# Instrutmentation_Design.net
KiCad netlist of a schematic drawn in Altium Designer
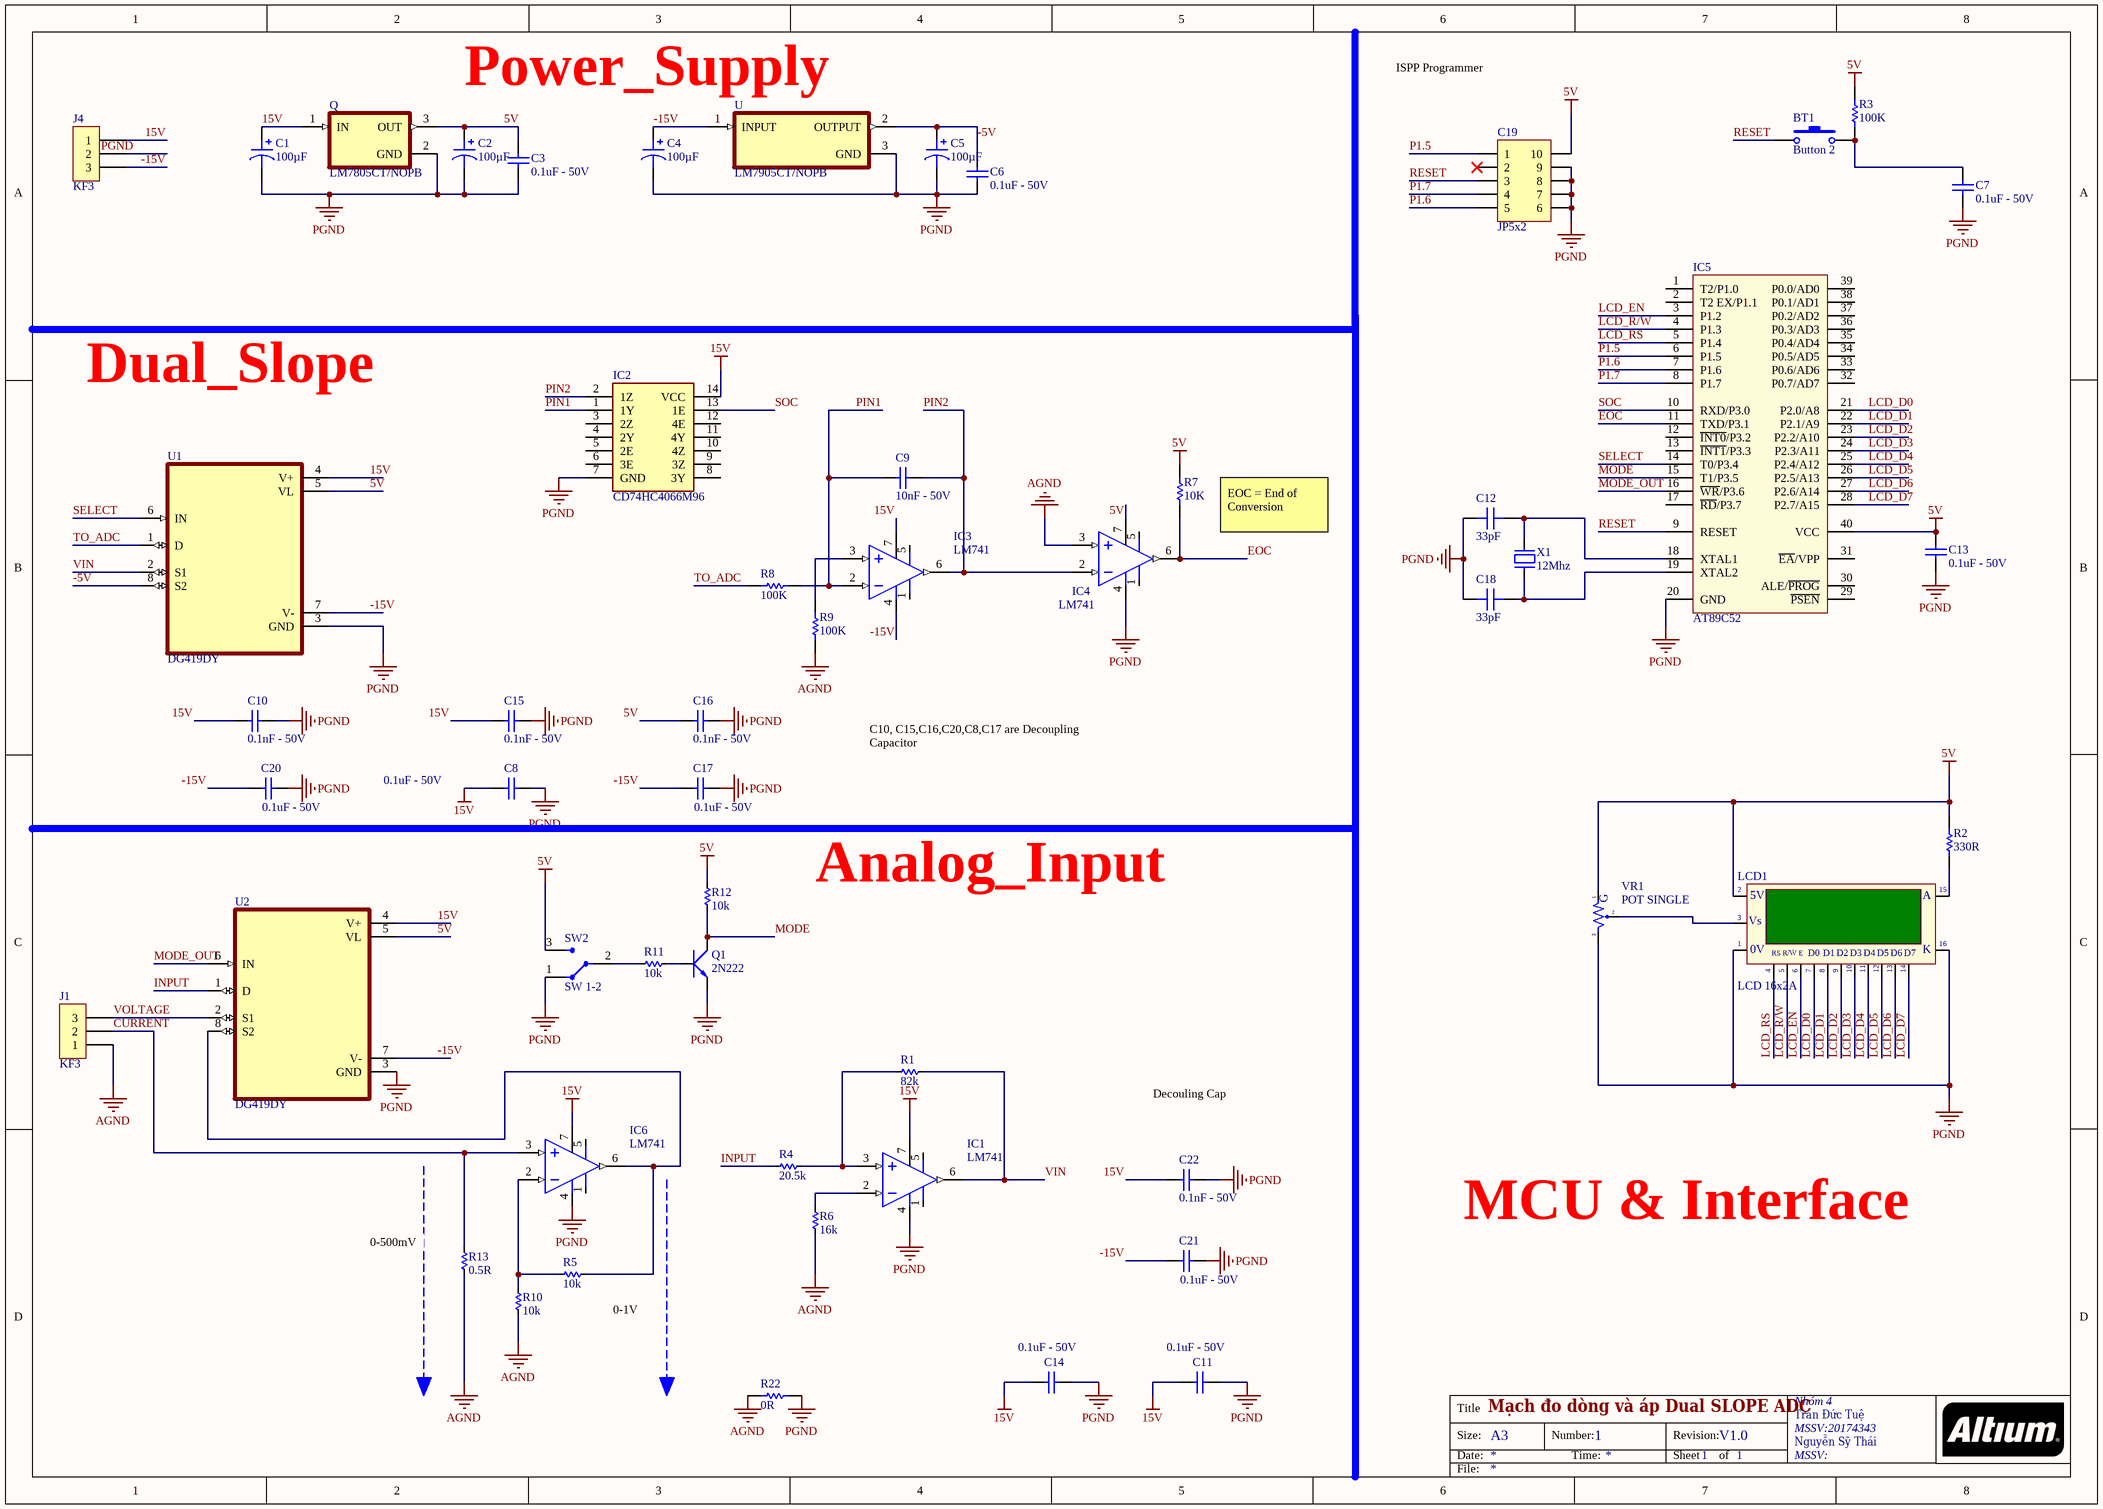
[diagram p0: Instrutmentation_Design.SchDoc]

(export (version "E")
  (design (tool "Eeschema 10.0.6"))
  (components
    (comp (ref "BT1")
      (value "Button 2")
      (footprint "4341x10438x6_6x3.5x4.3")
      (description "Button 2 Pin no Sheld")
      (libsource (lib "Library") (part "Button 2"))
    )
    (comp (ref "C1")
      (value "100µF")
      (footprint "CAP TH ALUM ELEC D8.00mm S3.50mm H12.50mm")
      (description "CAP ALUM 100UF 20% 50V RADIAL")
      (fields
        (field (name "PART NUMBER") "ECA-1HM101")
        (field (name "MANUFACTURER") "Panasonic Electronic Components")
      )
      (libsource (lib "Celestial Altium Library - altium_library") (part "Polarised Capacitor"))
    )
    (comp (ref "C2")
      (value "100µF")
      (footprint "CAP TH ALUM ELEC D8.00mm S3.50mm H12.50mm")
      (description "CAP ALUM 100UF 20% 50V RADIAL")
      (fields
        (field (name "PART NUMBER") "ECA-1HM101")
        (field (name "MANUFACTURER") "Panasonic Electronic Components")
      )
      (libsource (lib "Celestial Altium Library - altium_library") (part "Polarised Capacitor"))
    )
    (comp (ref "C3")
      (value "0.1uF - 50V")
      (footprint "CAPC_0603_N")
      (description "CAP CER 0.1UF 50V X7R 0603")
      (fields (field (name "PARTNUMBER") "C0603X7R104K500NT") (field (name "CREATOR") "ThangND"))
      (libsource (lib "MKP_lib") (part "CAP"))
    )
    (comp (ref "C4")
      (value "100µF")
      (footprint "CAP TH ALUM ELEC D8.00mm S3.50mm H12.50mm")
      (description "CAP ALUM 100UF 20% 50V RADIAL")
      (fields
        (field (name "PART NUMBER") "ECA-1HM101")
        (field (name "MANUFACTURER") "Panasonic Electronic Components")
      )
      (libsource (lib "Celestial Altium Library - altium_library") (part "Polarised Capacitor"))
    )
    (comp (ref "C5")
      (value "100µF")
      (footprint "CAP TH ALUM ELEC D8.00mm S3.50mm H12.50mm")
      (description "CAP ALUM 100UF 20% 50V RADIAL")
      (fields
        (field (name "PART NUMBER") "ECA-1HM101")
        (field (name "MANUFACTURER") "Panasonic Electronic Components")
      )
      (libsource (lib "Celestial Altium Library - altium_library") (part "Polarised Capacitor"))
    )
    (comp (ref "C6")
      (value "0.1uF - 50V")
      (footprint "CAPC_0603_N")
      (description "CAP CER 0.1UF 50V X7R 0603")
      (fields (field (name "PARTNUMBER") "C0603X7R104K500NT") (field (name "CREATOR") "ThangND"))
      (libsource (lib "MKP_lib") (part "CAP"))
    )
    (comp (ref "C7")
      (value "0.1uF - 50V")
      (footprint "CAPC_0603_N")
      (description "CAP CER 0.1UF 50V X7R 0603")
      (fields (field (name "PARTNUMBER") "C0603X7R104K500NT") (field (name "CREATOR") "ThangND"))
      (libsource (lib "MKP_lib") (part "CAP"))
    )
    (comp (ref "C8")
      (value "0.1uF - 50V")
      (footprint "CAPC_0603_N")
      (description "CAP CER 0.1UF 50V X7R 0603")
      (fields (field (name "PARTNUMBER") "C0603X7R104K500NT") (field (name "CREATOR") "ThangND"))
      (libsource (lib "MKP_lib") (part "CAP"))
    )
    (comp (ref "C9")
      (value "10nF - 50V")
      (footprint "CAPC_0603_N")
      (description "CAP CER 10000PF 50V X7R 0603")
      (fields (field (name "PARTNUMBER") "C0603X7R103J500NT") (field (name "CREATOR") "ThangND"))
      (libsource (lib "MKP_lib") (part "CAP"))
    )
    (comp (ref "C10")
      (value "0.1nF - 50V")
      (footprint "CAPC_0603_N")
      (description "CAP CER 100PF 50V X7R 0603")
      (fields (field (name "PARTNUMBER") "CL10B101KB8NNNC") (field (name "CREATOR") "ThangND"))
      (libsource (lib "MKP_lib") (part "CAP"))
    )
    (comp (ref "C11")
      (value "0.1uF - 50V")
      (footprint "CAPC_0603_N")
      (description "CAP CER 0.1UF 50V X7R 0603")
      (fields (field (name "PARTNUMBER") "C0603X7R104K500NT") (field (name "CREATOR") "ThangND"))
      (libsource (lib "MKP_lib") (part "CAP"))
    )
    (comp (ref "C12")
      (value "33pF")
      (footprint "CAP 0805_2012")
      (description "CAP CER 33PF 250V C0G/NP0 0805")
      (fields (field (name "PART NUMBER") "CBR08C330JAGAC") (field (name "MANUFACTURER") "KEMET"))
      (libsource (lib "Celestial Altium Library - altium_library") (part "Capacitor"))
    )
    (comp (ref "C13")
      (value "0.1uF - 50V")
      (footprint "CAPC_0603_N")
      (description "CAP CER 0.1UF 50V X7R 0603")
      (fields (field (name "PARTNUMBER") "C0603X7R104K500NT") (field (name "CREATOR") "ThangND"))
      (libsource (lib "MKP_lib") (part "CAP"))
    )
    (comp (ref "C14")
      (value "0.1uF - 50V")
      (footprint "CAPC_0603_N")
      (description "CAP CER 0.1UF 50V X7R 0603")
      (fields (field (name "PARTNUMBER") "C0603X7R104K500NT") (field (name "CREATOR") "ThangND"))
      (libsource (lib "MKP_lib") (part "CAP"))
    )
    (comp (ref "C15")
      (value "0.1nF - 50V")
      (footprint "CAPC_0603_N")
      (description "CAP CER 100PF 50V X7R 0603")
      (fields (field (name "PARTNUMBER") "CL10B101KB8NNNC") (field (name "CREATOR") "ThangND"))
      (libsource (lib "MKP_lib") (part "CAP"))
    )
    (comp (ref "C16")
      (value "0.1nF - 50V")
      (footprint "CAPC_0603_N")
      (description "CAP CER 100PF 50V X7R 0603")
      (fields (field (name "PARTNUMBER") "CL10B101KB8NNNC") (field (name "CREATOR") "ThangND"))
      (libsource (lib "MKP_lib") (part "CAP"))
    )
    (comp (ref "C17")
      (value "0.1uF - 50V")
      (footprint "CAPC_0603_N")
      (description "CAP CER 0.1UF 50V X7R 0603")
      (fields (field (name "PARTNUMBER") "CL10B104KB8NNNC") (field (name "CREATOR") "ThangND"))
      (libsource (lib "MKP_lib") (part "CAP"))
    )
    (comp (ref "C18")
      (value "33pF")
      (footprint "CAP 0805_2012")
      (description "CAP CER 33PF 250V C0G/NP0 0805")
      (fields (field (name "PART NUMBER") "CBR08C330JAGAC") (field (name "MANUFACTURER") "KEMET"))
      (libsource (lib "Celestial Altium Library - altium_library") (part "Capacitor"))
    )
    (comp (ref "C19")
      (value "JP5x2")
      (footprint "JP5-D2T")
      (description "WR-PHD 2.54 mm Dual Socket Header")
      (fields
        (field (name "MANUFACTURER") "Würth Elektronik eiSos GmbH")
        (field (name "PARTNO") "61301021821")
        (field (name "CREATED BY") "Karrer Zheng")
      )
      (libsource (lib "LIBRARY TuHu") (part "JP5x2"))
    )
    (comp (ref "C20")
      (value "0.1uF - 50V")
      (footprint "CAPC_0603_N")
      (description "CAP CER 0.1UF 50V X7R 0603")
      (fields (field (name "PARTNUMBER") "CL10B104KB8NNNC") (field (name "CREATOR") "ThangND"))
      (libsource (lib "MKP_lib") (part "CAP"))
    )
    (comp (ref "C21")
      (value "0.1uF - 50V")
      (footprint "CAPC_0603_N")
      (description "CAP CER 0.1UF 50V X7R 0603")
      (fields (field (name "PARTNUMBER") "CL10B104KB8NNNC") (field (name "CREATOR") "ThangND"))
      (libsource (lib "MKP_lib") (part "CAP"))
    )
    (comp (ref "C22")
      (value "0.1nF - 50V")
      (footprint "CAPC_0603_N")
      (description "CAP CER 100PF 50V X7R 0603")
      (fields (field (name "PARTNUMBER") "CL10B101KB8NNNC") (field (name "CREATOR") "ThangND"))
      (libsource (lib "MKP_lib") (part "CAP"))
    )
    (comp (ref "IC1")
      (value "LM741")
      (footprint "SO8")
      (description "Single OA")
      (libsource (lib "LIBRARY TuHu") (part "LM741"))
    )
    (comp (ref "IC2")
      (value "CD74HC4066M96")
      (footprint "SamacSys:SOIC127P600X175-14N")
      (description "Integrated Circuit")
      (fields (field (name "MOUSER PART NUMBER") "595-CD74HC4066M96"))
      (libsource (lib "*") (part "CD74HC4066M96"))
    )
    (comp (ref "IC3")
      (value "LM741")
      (footprint "SO8")
      (description "Single OA")
      (libsource (lib "LIBRARY TuHu") (part "LM741"))
    )
    (comp (ref "IC4")
      (value "LM741")
      (footprint "SO8")
      (description "Single OA")
      (libsource (lib "LIBRARY TuHu") (part "LM741"))
    )
    (comp (ref "IC5")
      (value "AT89C52")
      (footprint "DIP40/W0.6")
      (description "Atmel AT89C52, 8k Byte Flash Memory , 40 Pin")
      (libsource (lib "syhaunguyen") (part "AT89C52"))
    )
    (comp (ref "IC6")
      (value "LM741")
      (footprint "SO8")
      (description "Single OA")
      (libsource (lib "LIBRARY TuHu") (part "LM741"))
    )
    (comp (ref "J1")
      (value "KF3")
      (footprint "KF3-5.08")
      (fields
        (field (name "MANUFACTURER") "Würth Elektronik eiSos GmbH")
        (field (name "PARTNO") "691103110003")
        (field (name "CREATED BY") "Karrer Zheng")
      )
      (libsource (lib "LIBRARY TuHu") (part "KF3"))
    )
    (comp (ref "J4")
      (value "KF3")
      (footprint "KF3-5.08")
      (fields
        (field (name "MANUFACTURER") "Würth Elektronik eiSos GmbH")
        (field (name "PARTNO") "691103110003")
        (field (name "CREATED BY") "Karrer Zheng")
      )
      (libsource (lib "") (part "KF3_1"))
    )
    (comp (ref "LCD1")
      (value "LCD 16x2A")
      (footprint "JP16-C1T")
      (description "LCD dipslay 16 char, 2 line")
      (libsource (lib "LIBRARY TuHu") (part "LCD16x2A"))
    )
    (comp (ref "Q")
      (value "LM7805CT/NOPB")
      (footprint "SnapEDApcb:TO254P1054X470X2600-3")
      (description "Linear Voltage Regulator IC 1 Output 1A TO-220-3")
      (fields (field (name "MP") "LM7805CT") (field (name "MF") "ON Semiconductor"))
      (libsource (lib "SnapEDAsch") (part "LM7805CT/NOPB"))
    )
    (comp (ref "Q1")
      (value "2N222")
      (footprint "SOT23-231")
      (description "NPN 600mW, ECB")
      (libsource (lib "LIBRARY TuHu") (part "2N222"))
    )
    (comp (ref "R1")
      (value "82k")
      (footprint "RES-SMD-0805")
      (description "Resistor")
      (fields
        (field (name "MANUFACTURER") "Generic Components")
        (field (name "PUBLISHER") "Altium Hobart Technology Centre")
      )
      (libsource (lib "LIBRARY TuHu") (part "Res-SMD"))
    )
    (comp (ref "R2")
      (value "330R")
      (footprint "RESC_0603_N")
      (description "RES SMD 330 OHM 1% 1/10W 0603")
      (fields (field (name "PARTNUMBER") "RI0603L3300FT") (field (name "CREATOR") "anhdn"))
      (libsource (lib "MKP_lib") (part "RES"))
    )
    (comp (ref "R3")
      (value "100K")
      (footprint "RESC_0805_N")
      (description "RES SMD 100K OHM 5% 1/8W 0805")
      (fields (field (name "PARTNUMBER") "RC0805JR-07100KL") (field (name "CREATOR") "Tunn"))
      (libsource (lib "MKP_lib") (part "RES"))
    )
    (comp (ref "R4")
      (value "20.5k")
      (footprint "RES-SMD-0805")
      (description "Resistor")
      (fields
        (field (name "MANUFACTURER") "Generic Components")
        (field (name "PUBLISHER") "Altium Hobart Technology Centre")
      )
      (libsource (lib "LIBRARY TuHu") (part "Res-SMD"))
    )
    (comp (ref "R5")
      (value "10k")
      (footprint "RES-SMD-0805")
      (description "Resistor")
      (fields
        (field (name "MANUFACTURER") "Generic Components")
        (field (name "PUBLISHER") "Altium Hobart Technology Centre")
      )
      (libsource (lib "LIBRARY TuHu") (part "Res-SMD"))
    )
    (comp (ref "R6")
      (value "16k")
      (footprint "RES-SMD-0805")
      (description "Resistor")
      (fields
        (field (name "MANUFACTURER") "Generic Components")
        (field (name "PUBLISHER") "Altium Hobart Technology Centre")
      )
      (libsource (lib "LIBRARY TuHu") (part "Res-SMD"))
    )
    (comp (ref "R7")
      (value "10K")
      (footprint "RESC_0603_N")
      (description "RES SMD 10K OHM 1% 1/10W 0603")
      (fields (field (name "PARTNUMBER") "RI0603L1002FT") (field (name "CREATOR") "anhdn"))
      (libsource (lib "MKP_lib") (part "RES"))
    )
    (comp (ref "R8")
      (value "100K")
      (footprint "RESC_0805_N")
      (description "RES SMD 100K OHM 5% 1/8W 0805")
      (fields (field (name "PARTNUMBER") "RC0805JR-07100KL") (field (name "CREATOR") "Tunn"))
      (libsource (lib "MKP_lib") (part "RES"))
    )
    (comp (ref "R9")
      (value "100K")
      (footprint "RESC_0805_N")
      (description "RES SMD 100K OHM 5% 1/8W 0805")
      (fields (field (name "PARTNUMBER") "RC0805JR-07100KL") (field (name "CREATOR") "Tunn"))
      (libsource (lib "MKP_lib") (part "RES"))
    )
    (comp (ref "R10")
      (value "10k")
      (footprint "RES-SMD-0805")
      (description "Resistor")
      (fields
        (field (name "MANUFACTURER") "Generic Components")
        (field (name "PUBLISHER") "Altium Hobart Technology Centre")
      )
      (libsource (lib "LIBRARY TuHu") (part "Res-SMD"))
    )
    (comp (ref "R11")
      (value "10k")
      (footprint "RES-SMD-0805")
      (description "Resistor")
      (fields
        (field (name "MANUFACTURER") "Generic Components")
        (field (name "PUBLISHER") "Altium Hobart Technology Centre")
      )
      (libsource (lib "LIBRARY TuHu") (part "Res-SMD"))
    )
    (comp (ref "R12")
      (value "10k")
      (footprint "RES-SMD-0805")
      (description "Resistor")
      (fields
        (field (name "MANUFACTURER") "Generic Components")
        (field (name "PUBLISHER") "Altium Hobart Technology Centre")
      )
      (libsource (lib "LIBRARY TuHu") (part "Res-SMD"))
    )
    (comp (ref "R13")
      (value "0.5R")
      (footprint "RES-SMD-1206")
      (description "Resistor")
      (fields
        (field (name "MANUFACTURER") "Generic Components")
        (field (name "PUBLISHER") "Altium Hobart Technology Centre")
      )
      (libsource (lib "LIBRARY TuHu") (part "Res-SMD"))
    )
    (comp (ref "R22")
      (value "0R")
      (footprint "RESC_0805_N")
      (description "RES SMD 0 OHM JUMPER 1/8W 0805")
      (fields (field (name "PARTNUMBER") "RC0805JR-070RL") (field (name "CREATOR") "anhdn"))
      (libsource (lib "MKP_lib") (part "RES"))
    )
    (comp (ref "SW2")
      (value "SW 1-2")
      (footprint "450301014042")
      (description "Switch 1-2 Pin")
      (libsource (lib "Library") (part "SW 1-2"))
    )
    (comp (ref "U")
      (value "LM7905CT/NOPB")
      (footprint "TO254P1054X470X1955-3:TO254P1054X470X1955-3")
      (description "1.5-A, negative linear voltage regulator 3-TO-220 0 to 125")
      (fields (field (name "MF") "Texas Instruments"))
      (libsource (lib "LM7905CT_NOPB") (part "LM7905CT/NOPB"))
    )
    (comp (ref "U1")
      (value "DG419DY")
      (footprint "SOIC127P600X175-8N:SOIC127P600X175-8N")
      (libsource (lib "DG419DY") (part "DG419DY"))
    )
    (comp (ref "U2")
      (value "DG419DY")
      (footprint "SOIC127P600X175-8N:SOIC127P600X175-8N")
      (libsource (lib "DG419DY") (part "DG419DY"))
    )
    (comp (ref "VR1")
      (value "POT SINGLE")
      (footprint "POTSD 3296V")
      (description "Var Resistor")
      (libsource (lib "Library") (part "POT SINGLE"))
    )
    (comp (ref "X1")
      (value "12Mhz")
      (footprint "XT2")
      (description "Crystal, 32.768 KHz, -40 to 85 degC, 3.2 x 1.5 x 0.9 mm SMD")
      (libsource (lib "LIBRARY TuHu") (part "XT2"))
    )
  )
  (nets
    (net (code "1") (name "/-5V") (class "Default")
      (node (ref "C5") (pin "1") (pinfunction "1_1") (pintype "passive"))
      (node (ref "C6") (pin "2") (pinfunction "2_2") (pintype "passive"))
      (node (ref "U") (pin "2") (pinfunction "OUTPUT_2") (pintype "output"))
      (node (ref "U1") (pin "8") (pinfunction "S2_8") (pintype "bidirectional"))
    )
    (net (code "2") (name "/-15V") (class "Default")
      (node (ref "C17") (pin "1") (pinfunction "1_1") (pintype "passive"))
      (node (ref "C20") (pin "1") (pinfunction "1_1") (pintype "passive"))
      (node (ref "C21") (pin "1") (pinfunction "1_1") (pintype "passive"))
      (node (ref "C4") (pin "1") (pinfunction "1_1") (pintype "passive"))
      (node (ref "IC3") (pin "4") (pinfunction "-V_4") (pintype "passive"))
      (node (ref "J4") (pin "3") (pinfunction "3_3") (pintype "passive"))
      (node (ref "U") (pin "1") (pinfunction "INPUT_1") (pintype "input"))
      (node (ref "U1") (pin "7") (pinfunction "V-_7") (pintype "power_in"))
      (node (ref "U2") (pin "7") (pinfunction "V-_7") (pintype "power_in"))
    )
    (net (code "3") (name "/CURRENT") (class "Default")
      (node (ref "IC6") (pin "3") (pinfunction "IN+_3") (pintype "input"))
      (node (ref "J1") (pin "2") (pinfunction "2_2") (pintype "passive"))
      (node (ref "R13") (pin "2") (pinfunction "2_2") (pintype "passive"))
    )
    (net (code "4") (name "/EOC") (class "Default")
      (node (ref "IC4") (pin "6") (pinfunction "OUT_6") (pintype "output"))
      (node (ref "IC5") (pin "11") (pinfunction "TXD/P3.1_11") (pintype "passive"))
      (node (ref "R7") (pin "2") (pinfunction "2_2") (pintype "passive"))
    )
    (net (code "5") (name "/INPUT") (class "Default")
      (node (ref "R4") (pin "1") (pinfunction "1_1") (pintype "passive"))
      (node (ref "U2") (pin "1") (pinfunction "D_1") (pintype "bidirectional"))
    )
    (net (code "6") (name "/LCD_D0") (class "Default")
      (node (ref "IC5") (pin "21") (pinfunction "P2.0/A8_21") (pintype "passive"))
      (node (ref "LCD1") (pin "7") (pinfunction "D0_7") (pintype "passive"))
    )
    (net (code "7") (name "/LCD_D1") (class "Default")
      (node (ref "IC5") (pin "22") (pinfunction "P2.1/A9_22") (pintype "passive"))
      (node (ref "LCD1") (pin "8") (pinfunction "D1_8") (pintype "passive"))
    )
    (net (code "8") (name "/LCD_D2") (class "Default")
      (node (ref "IC5") (pin "23") (pinfunction "P2.2/A10_23") (pintype "passive"))
      (node (ref "LCD1") (pin "9") (pinfunction "D2_9") (pintype "passive"))
    )
    (net (code "9") (name "/LCD_D3") (class "Default")
      (node (ref "IC5") (pin "24") (pinfunction "P2.3/A11_24") (pintype "passive"))
      (node (ref "LCD1") (pin "10") (pinfunction "D3_10") (pintype "passive"))
    )
    (net (code "10") (name "/LCD_D4") (class "Default")
      (node (ref "IC5") (pin "25") (pinfunction "P2.4/A12_25") (pintype "passive"))
      (node (ref "LCD1") (pin "11") (pinfunction "D4_11") (pintype "passive"))
    )
    (net (code "11") (name "/LCD_D5") (class "Default")
      (node (ref "IC5") (pin "26") (pinfunction "P2.5/A13_26") (pintype "passive"))
      (node (ref "LCD1") (pin "12") (pinfunction "D5_12") (pintype "passive"))
    )
    (net (code "12") (name "/LCD_D6") (class "Default")
      (node (ref "IC5") (pin "27") (pinfunction "P2.6/A14_27") (pintype "passive"))
      (node (ref "LCD1") (pin "13") (pinfunction "D6_13") (pintype "passive"))
    )
    (net (code "13") (name "/LCD_D7") (class "Default")
      (node (ref "IC5") (pin "28") (pinfunction "P2.7/A15_28") (pintype "passive"))
      (node (ref "LCD1") (pin "14") (pinfunction "D7_14") (pintype "passive"))
    )
    (net (code "14") (name "/LCD_EN") (class "Default")
      (node (ref "IC5") (pin "3") (pinfunction "P1.2_3") (pintype "passive"))
      (node (ref "LCD1") (pin "6") (pinfunction "~{EN}_6") (pintype "passive"))
    )
    (net (code "15") (name "/LCD_RS") (class "Default")
      (node (ref "IC5") (pin "5") (pinfunction "P1.4_5") (pintype "passive"))
      (node (ref "LCD1") (pin "4") (pinfunction "RS_4") (pintype "passive"))
    )
    (net (code "16") (name "/LCD_R{slash}~{W}") (class "Default")
      (node (ref "IC5") (pin "4") (pinfunction "P1.3_4") (pintype "passive"))
      (node (ref "LCD1") (pin "5") (pinfunction "R/~{W}_5") (pintype "passive"))
    )
    (net (code "17") (name "/MODE") (class "Default")
      (node (ref "IC5") (pin "15") (pinfunction "T1/P3.5_15") (pintype "passive"))
      (node (ref "Q1") (pin "3") (pinfunction "C_3") (pintype "passive"))
      (node (ref "R12") (pin "1") (pinfunction "1_1") (pintype "passive"))
    )
    (net (code "18") (name "/MODE_OUT") (class "Default")
      (node (ref "IC5") (pin "16") (pinfunction "~{WR}/P3.6_16") (pintype "passive"))
      (node (ref "U2") (pin "6") (pinfunction "IN_6") (pintype "input"))
    )
    (net (code "19") (name "/P1.5") (class "Default")
      (node (ref "C19") (pin "1") (pinfunction "1_1") (pintype "passive"))
      (node (ref "IC5") (pin "6") (pinfunction "P1.5_6") (pintype "passive"))
    )
    (net (code "20") (name "/P1.6") (class "Default")
      (node (ref "C19") (pin "5") (pinfunction "5_5") (pintype "passive"))
      (node (ref "IC5") (pin "7") (pinfunction "P1.6_7") (pintype "passive"))
    )
    (net (code "21") (name "/P1.7") (class "Default")
      (node (ref "C19") (pin "4") (pinfunction "4_4") (pintype "passive"))
      (node (ref "IC5") (pin "8") (pinfunction "P1.7_8") (pintype "passive"))
    )
    (net (code "22") (name "/PIN1") (class "Default")
      (node (ref "C9") (pin "1") (pinfunction "1_1") (pintype "passive"))
      (node (ref "IC2") (pin "1") (pinfunction "1Y_1") (pintype "passive"))
      (node (ref "IC3") (pin "2") (pinfunction "IN-_2") (pintype "input"))
      (node (ref "R8") (pin "1") (pinfunction "1_1") (pintype "passive"))
    )
    (net (code "23") (name "/PIN2") (class "Default")
      (node (ref "C9") (pin "2") (pinfunction "2_2") (pintype "passive"))
      (node (ref "IC2") (pin "2") (pinfunction "1Z_2") (pintype "passive"))
      (node (ref "IC3") (pin "6") (pinfunction "OUT_6") (pintype "output"))
      (node (ref "IC4") (pin "2") (pinfunction "IN-_2") (pintype "input"))
    )
    (net (code "24") (name "/RESET") (class "Default")
      (node (ref "BT1") (pin "1") (pinfunction "1_1") (pintype "passive"))
      (node (ref "C19") (pin "3") (pinfunction "3_3") (pintype "passive"))
      (node (ref "IC5") (pin "9") (pinfunction "RESET_9") (pintype "passive"))
    )
    (net (code "25") (name "/SELECT") (class "Default")
      (node (ref "IC5") (pin "14") (pinfunction "T0/P3.4_14") (pintype "passive"))
      (node (ref "U1") (pin "6") (pinfunction "IN_6") (pintype "input"))
    )
    (net (code "26") (name "/SOC") (class "Default")
      (node (ref "IC2") (pin "13") (pinfunction "1E_13") (pintype "passive"))
      (node (ref "IC5") (pin "10") (pinfunction "RXD/P3.0_10") (pintype "passive"))
    )
    (net (code "27") (name "/TO_ADC") (class "Default")
      (node (ref "R8") (pin "2") (pinfunction "2_2") (pintype "passive"))
      (node (ref "U1") (pin "1") (pinfunction "D_1") (pintype "bidirectional"))
    )
    (net (code "28") (name "/VIN") (class "Default")
      (node (ref "IC1") (pin "6") (pinfunction "OUT_6") (pintype "output"))
      (node (ref "R1") (pin "2") (pinfunction "2_2") (pintype "passive"))
      (node (ref "U1") (pin "2") (pinfunction "S1_2") (pintype "bidirectional"))
    )
    (net (code "29") (name "/VOLTAGE") (class "Default")
      (node (ref "J1") (pin "3") (pinfunction "3_3") (pintype "passive"))
      (node (ref "U2") (pin "2") (pinfunction "S1_2") (pintype "bidirectional"))
    )
    (net (code "30") (name "5V") (class "Default")
      (node (ref "C13") (pin "1") (pinfunction "1_1") (pintype "passive"))
      (node (ref "C16") (pin "1") (pinfunction "1_1") (pintype "passive"))
      (node (ref "C19") (pin "10") (pinfunction "10_10") (pintype "passive"))
      (node (ref "C2") (pin "1") (pinfunction "1_1") (pintype "passive"))
      (node (ref "C3") (pin "2") (pinfunction "2_2") (pintype "passive"))
      (node (ref "IC4") (pin "7") (pinfunction "+V_7") (pintype "passive"))
      (node (ref "IC5") (pin "40") (pinfunction "VCC_40") (pintype "power_in"))
      (node (ref "LCD1") (pin "2") (pinfunction "VDD_2") (pintype "passive"))
      (node (ref "Q") (pin "3") (pinfunction "OUT_3") (pintype "output"))
      (node (ref "R12") (pin "2") (pinfunction "2_2") (pintype "passive"))
      (node (ref "R2") (pin "1") (pinfunction "1_1") (pintype "passive"))
      (node (ref "R3") (pin "1") (pinfunction "1_1") (pintype "passive"))
      (node (ref "R7") (pin "1") (pinfunction "1_1") (pintype "passive"))
      (node (ref "SW2") (pin "3") (pinfunction "I/O2_3") (pintype "passive"))
      (node (ref "U1") (pin "5") (pinfunction "VL_5") (pintype "power_in"))
      (node (ref "U2") (pin "5") (pinfunction "VL_5") (pintype "power_in"))
      (node (ref "VR1") (pin "1") (pinfunction "1_1") (pintype "passive"))
    )
    (net (code "31") (name "15V") (class "Default")
      (node (ref "C1") (pin "1") (pinfunction "1_1") (pintype "passive"))
      (node (ref "C10") (pin "1") (pinfunction "1_1") (pintype "passive"))
      (node (ref "C11") (pin "1") (pinfunction "1_1") (pintype "passive"))
      (node (ref "C14") (pin "1") (pinfunction "1_1") (pintype "passive"))
      (node (ref "C15") (pin "1") (pinfunction "1_1") (pintype "passive"))
      (node (ref "C22") (pin "1") (pinfunction "1_1") (pintype "passive"))
      (node (ref "C8") (pin "1") (pinfunction "1_1") (pintype "passive"))
      (node (ref "IC1") (pin "7") (pinfunction "+V_7") (pintype "passive"))
      (node (ref "IC2") (pin "14") (pinfunction "VCC_14") (pintype "passive"))
      (node (ref "IC3") (pin "7") (pinfunction "+V_7") (pintype "passive"))
      (node (ref "IC6") (pin "7") (pinfunction "+V_7") (pintype "passive"))
      (node (ref "J4") (pin "1") (pinfunction "1_1") (pintype "passive"))
      (node (ref "Q") (pin "1") (pinfunction "IN_1") (pintype "input"))
      (node (ref "U1") (pin "4") (pinfunction "V+_4") (pintype "power_in"))
      (node (ref "U2") (pin "4") (pinfunction "V+_4") (pintype "power_in"))
    )
    (net (code "32") (name "AGND") (class "Default")
      (node (ref "IC4") (pin "3") (pinfunction "IN+_3") (pintype "input"))
      (node (ref "J1") (pin "1") (pinfunction "1_1") (pintype "passive"))
      (node (ref "R10") (pin "2") (pinfunction "2_2") (pintype "passive"))
      (node (ref "R13") (pin "1") (pinfunction "1_1") (pintype "passive"))
      (node (ref "R22") (pin "2") (pinfunction "2_2") (pintype "passive"))
      (node (ref "R6") (pin "2") (pinfunction "2_2") (pintype "passive"))
      (node (ref "R9") (pin "2") (pinfunction "2_2") (pintype "passive"))
    )
    (net (code "33") (name "Net-(BT1-Pad2)") (class "Default")
      (node (ref "BT1") (pin "2") (pinfunction "2_2") (pintype "passive"))
      (node (ref "C7") (pin "2") (pinfunction "2_2") (pintype "passive"))
      (node (ref "R3") (pin "2") (pinfunction "2_2") (pintype "passive"))
    )
    (net (code "34") (name "Net-(IC1-IN+)") (class "Default")
      (node (ref "IC1") (pin "3") (pinfunction "IN+_3") (pintype "input"))
      (node (ref "R1") (pin "1") (pinfunction "1_1") (pintype "passive"))
      (node (ref "R4") (pin "2") (pinfunction "2_2") (pintype "passive"))
    )
    (net (code "35") (name "Net-(IC1-IN-)") (class "Default")
      (node (ref "IC1") (pin "2") (pinfunction "IN-_2") (pintype "input"))
      (node (ref "R6") (pin "1") (pinfunction "1_1") (pintype "passive"))
    )
    (net (code "36") (name "Net-(IC3-IN+)") (class "Default")
      (node (ref "IC3") (pin "3") (pinfunction "IN+_3") (pintype "input"))
      (node (ref "R9") (pin "1") (pinfunction "1_1") (pintype "passive"))
    )
    (net (code "37") (name "Net-(IC5-XTAL1)") (class "Default")
      (node (ref "C12") (pin "2") (pinfunction "2_2") (pintype "passive"))
      (node (ref "IC5") (pin "18") (pinfunction "XTAL1_18") (pintype "passive"))
      (node (ref "X1") (pin "2") (pinfunction "2_2") (pintype "passive"))
    )
    (net (code "38") (name "Net-(IC5-XTAL2)") (class "Default")
      (node (ref "C18") (pin "2") (pinfunction "2_2") (pintype "passive"))
      (node (ref "IC5") (pin "19") (pinfunction "XTAL2_19") (pintype "passive"))
      (node (ref "X1") (pin "1") (pinfunction "1_1") (pintype "passive"))
    )
    (net (code "39") (name "Net-(IC6-IN-)") (class "Default")
      (node (ref "IC6") (pin "2") (pinfunction "IN-_2") (pintype "input"))
      (node (ref "R10") (pin "1") (pinfunction "1_1") (pintype "passive"))
      (node (ref "R5") (pin "1") (pinfunction "1_1") (pintype "passive"))
    )
    (net (code "40") (name "Net-(IC6-OUT)") (class "Default")
      (node (ref "IC6") (pin "6") (pinfunction "OUT_6") (pintype "output"))
      (node (ref "R5") (pin "2") (pinfunction "2_2") (pintype "passive"))
      (node (ref "U2") (pin "8") (pinfunction "S2_8") (pintype "bidirectional"))
    )
    (net (code "41") (name "Net-(LCD1-A)") (class "Default")
      (node (ref "LCD1") (pin "15") (pinfunction "A_15") (pintype "passive"))
      (node (ref "R2") (pin "2") (pinfunction "2_2") (pintype "passive"))
    )
    (net (code "42") (name "Net-(LCD1-VEE)") (class "Default")
      (node (ref "LCD1") (pin "3") (pinfunction "VEE_3") (pintype "passive"))
      (node (ref "VR1") (pin "2") (pinfunction "2_2") (pintype "passive"))
    )
    (net (code "43") (name "Net-(Q1-B)") (class "Default")
      (node (ref "Q1") (pin "2") (pinfunction "B_2") (pintype "passive"))
      (node (ref "R11") (pin "2") (pinfunction "2_2") (pintype "passive"))
    )
    (net (code "44") (name "Net-(R11-Pad1)") (class "Default")
      (node (ref "R11") (pin "1") (pinfunction "1_1") (pintype "passive"))
      (node (ref "SW2") (pin "2") (pintype "passive"))
    )
    (net (code "45") (name "PGND") (class "Default")
      (node (ref "C1") (pin "2") (pinfunction "2_2") (pintype "passive"))
      (node (ref "C10") (pin "2") (pinfunction "2_2") (pintype "passive"))
      (node (ref "C11") (pin "2") (pinfunction "2_2") (pintype "passive"))
      (node (ref "C12") (pin "1") (pinfunction "1_1") (pintype "passive"))
      (node (ref "C13") (pin "2") (pinfunction "2_2") (pintype "passive"))
      (node (ref "C14") (pin "2") (pinfunction "2_2") (pintype "passive"))
      (node (ref "C15") (pin "2") (pinfunction "2_2") (pintype "passive"))
      (node (ref "C16") (pin "2") (pinfunction "2_2") (pintype "passive"))
      (node (ref "C17") (pin "2") (pinfunction "2_2") (pintype "passive"))
      (node (ref "C18") (pin "1") (pinfunction "1_1") (pintype "passive"))
      (node (ref "C19") (pin "6") (pinfunction "6_6") (pintype "passive"))
      (node (ref "C19") (pin "7") (pinfunction "7_7") (pintype "passive"))
      (node (ref "C19") (pin "8") (pinfunction "8_8") (pintype "passive"))
      (node (ref "C19") (pin "9") (pinfunction "9_9") (pintype "passive"))
      (node (ref "C2") (pin "2") (pinfunction "2_2") (pintype "passive"))
      (node (ref "C20") (pin "2") (pinfunction "2_2") (pintype "passive"))
      (node (ref "C21") (pin "2") (pinfunction "2_2") (pintype "passive"))
      (node (ref "C22") (pin "2") (pinfunction "2_2") (pintype "passive"))
      (node (ref "C3") (pin "1") (pinfunction "1_1") (pintype "passive"))
      (node (ref "C4") (pin "2") (pinfunction "2_2") (pintype "passive"))
      (node (ref "C5") (pin "2") (pinfunction "2_2") (pintype "passive"))
      (node (ref "C6") (pin "1") (pinfunction "1_1") (pintype "passive"))
      (node (ref "C7") (pin "1") (pinfunction "1_1") (pintype "passive"))
      (node (ref "C8") (pin "2") (pinfunction "2_2") (pintype "passive"))
      (node (ref "IC1") (pin "4") (pinfunction "-V_4") (pintype "passive"))
      (node (ref "IC2") (pin "7") (pinfunction "GND_7") (pintype "passive"))
      (node (ref "IC4") (pin "4") (pinfunction "-V_4") (pintype "passive"))
      (node (ref "IC5") (pin "20") (pinfunction "GND_20") (pintype "open_emitter"))
      (node (ref "IC6") (pin "4") (pinfunction "-V_4") (pintype "passive"))
      (node (ref "J4") (pin "2") (pinfunction "2_2") (pintype "passive"))
      (node (ref "LCD1") (pin "1") (pinfunction "GND_1") (pintype "passive"))
      (node (ref "LCD1") (pin "16") (pinfunction "K_16") (pintype "passive"))
      (node (ref "Q") (pin "2") (pinfunction "GND_2") (pintype "power_in"))
      (node (ref "Q1") (pin "1") (pinfunction "E_1") (pintype "passive"))
      (node (ref "R22") (pin "1") (pinfunction "1_1") (pintype "passive"))
      (node (ref "SW2") (pin "1") (pintype "passive"))
      (node (ref "U") (pin "3") (pinfunction "GND_3") (pintype "power_in"))
      (node (ref "U1") (pin "3") (pinfunction "GND_3") (pintype "power_in"))
      (node (ref "U2") (pin "3") (pinfunction "GND_3") (pintype "power_in"))
      (node (ref "VR1") (pin "3") (pinfunction "3_3") (pintype "passive"))
    )
    (net (code "46") (name "unconnected-(C19-Pad2)") (class "Default")
      (node (ref "C19") (pin "2") (pinfunction "2_2") (pintype "passive+no_connect"))
    )
    (net (code "47") (name "unconnected-(IC1-Vos-Pad1)") (class "Default")
      (node (ref "IC1") (pin "1") (pinfunction "Vos_1") (pintype "passive"))
    )
    (net (code "48") (name "unconnected-(IC1-Vos-Pad5)") (class "Default")
      (node (ref "IC1") (pin "5") (pinfunction "Vos_5") (pintype "passive"))
    )
    (net (code "49") (name "unconnected-(IC2-2E-Pad5)") (class "Default")
      (node (ref "IC2") (pin "5") (pinfunction "2E_5") (pintype "passive"))
    )
    (net (code "50") (name "unconnected-(IC2-2Y-Pad4)") (class "Default")
      (node (ref "IC2") (pin "4") (pinfunction "2Y_4") (pintype "passive"))
    )
    (net (code "51") (name "unconnected-(IC2-2Z-Pad3)") (class "Default")
      (node (ref "IC2") (pin "3") (pinfunction "2Z_3") (pintype "passive"))
    )
    (net (code "52") (name "unconnected-(IC2-3E-Pad6)") (class "Default")
      (node (ref "IC2") (pin "6") (pinfunction "3E_6") (pintype "passive"))
    )
    (net (code "53") (name "unconnected-(IC2-3Y-Pad8)") (class "Default")
      (node (ref "IC2") (pin "8") (pinfunction "3Y_8") (pintype "passive"))
    )
    (net (code "54") (name "unconnected-(IC2-3Z-Pad9)") (class "Default")
      (node (ref "IC2") (pin "9") (pinfunction "3Z_9") (pintype "passive"))
    )
    (net (code "55") (name "unconnected-(IC2-4E-Pad12)") (class "Default")
      (node (ref "IC2") (pin "12") (pinfunction "4E_12") (pintype "passive"))
    )
    (net (code "56") (name "unconnected-(IC2-4Y-Pad11)") (class "Default")
      (node (ref "IC2") (pin "11") (pinfunction "4Y_11") (pintype "passive"))
    )
    (net (code "57") (name "unconnected-(IC2-4Z-Pad10)") (class "Default")
      (node (ref "IC2") (pin "10") (pinfunction "4Z_10") (pintype "passive"))
    )
    (net (code "58") (name "unconnected-(IC3-Vos-Pad1)") (class "Default")
      (node (ref "IC3") (pin "1") (pinfunction "Vos_1") (pintype "passive"))
    )
    (net (code "59") (name "unconnected-(IC3-Vos-Pad5)") (class "Default")
      (node (ref "IC3") (pin "5") (pinfunction "Vos_5") (pintype "passive"))
    )
    (net (code "60") (name "unconnected-(IC4-Vos-Pad1)") (class "Default")
      (node (ref "IC4") (pin "1") (pinfunction "Vos_1") (pintype "passive"))
    )
    (net (code "61") (name "unconnected-(IC4-Vos-Pad5)") (class "Default")
      (node (ref "IC4") (pin "5") (pinfunction "Vos_5") (pintype "passive"))
    )
    (net (code "62") (name "unconnected-(IC5-ALE{slash}~{PROG}-Pad30)") (class "Default")
      (node (ref "IC5") (pin "30") (pinfunction "ALE/~{PROG}_30") (pintype "passive"))
    )
    (net (code "63") (name "unconnected-(IC5-P0.0{slash}AD0-Pad39)") (class "Default")
      (node (ref "IC5") (pin "39") (pinfunction "P0.0/AD0_39") (pintype "passive"))
    )
    (net (code "64") (name "unconnected-(IC5-P0.1{slash}AD1-Pad38)") (class "Default")
      (node (ref "IC5") (pin "38") (pinfunction "P0.1/AD1_38") (pintype "passive"))
    )
    (net (code "65") (name "unconnected-(IC5-P0.2{slash}AD2-Pad37)") (class "Default")
      (node (ref "IC5") (pin "37") (pinfunction "P0.2/AD2_37") (pintype "passive"))
    )
    (net (code "66") (name "unconnected-(IC5-P0.3{slash}AD3-Pad36)") (class "Default")
      (node (ref "IC5") (pin "36") (pinfunction "P0.3/AD3_36") (pintype "passive"))
    )
    (net (code "67") (name "unconnected-(IC5-P0.4{slash}AD4-Pad35)") (class "Default")
      (node (ref "IC5") (pin "35") (pinfunction "P0.4/AD4_35") (pintype "passive"))
    )
    (net (code "68") (name "unconnected-(IC5-P0.5{slash}AD5-Pad34)") (class "Default")
      (node (ref "IC5") (pin "34") (pinfunction "P0.5/AD5_34") (pintype "passive"))
    )
    (net (code "69") (name "unconnected-(IC5-P0.6{slash}AD6-Pad33)") (class "Default")
      (node (ref "IC5") (pin "33") (pinfunction "P0.6/AD6_33") (pintype "passive"))
    )
    (net (code "70") (name "unconnected-(IC5-P0.7{slash}AD7-Pad32)") (class "Default")
      (node (ref "IC5") (pin "32") (pinfunction "P0.7/AD7_32") (pintype "passive"))
    )
    (net (code "71") (name "unconnected-(IC5-T2_EX{slash}P1.1-Pad2)") (class "Default")
      (node (ref "IC5") (pin "2") (pinfunction "T2_EX/P1.1_2") (pintype "passive"))
    )
    (net (code "72") (name "unconnected-(IC5-T2{slash}P1.0-Pad1)") (class "Default")
      (node (ref "IC5") (pin "1") (pinfunction "T2/P1.0_1") (pintype "passive"))
    )
    (net (code "73") (name "unconnected-(IC5-~{EA}{slash}VPP-Pad31)") (class "Default")
      (node (ref "IC5") (pin "31") (pinfunction "~{EA}/VPP_31") (pintype "passive"))
    )
    (net (code "74") (name "unconnected-(IC5-~{INT0}{slash}P3.2-Pad12)") (class "Default")
      (node (ref "IC5") (pin "12") (pinfunction "~{INT0}/P3.2_12") (pintype "passive"))
    )
    (net (code "75") (name "unconnected-(IC5-~{INT1}{slash}P3.3-Pad13)") (class "Default")
      (node (ref "IC5") (pin "13") (pinfunction "~{INT1}/P3.3_13") (pintype "passive"))
    )
    (net (code "76") (name "unconnected-(IC5-~{PSEN}-Pad29)") (class "Default")
      (node (ref "IC5") (pin "29") (pinfunction "~{PSEN}_29") (pintype "passive"))
    )
    (net (code "77") (name "unconnected-(IC5-~{RD}{slash}P3.7-Pad17)") (class "Default")
      (node (ref "IC5") (pin "17") (pinfunction "~{RD}/P3.7_17") (pintype "passive"))
    )
    (net (code "78") (name "unconnected-(IC6-Vos-Pad1)") (class "Default")
      (node (ref "IC6") (pin "1") (pinfunction "Vos_1") (pintype "passive"))
    )
    (net (code "79") (name "unconnected-(IC6-Vos-Pad5)") (class "Default")
      (node (ref "IC6") (pin "5") (pinfunction "Vos_5") (pintype "passive"))
    )
  )
)
